# power.net
KiCad netlist of a schematic drawn in Altium Designer
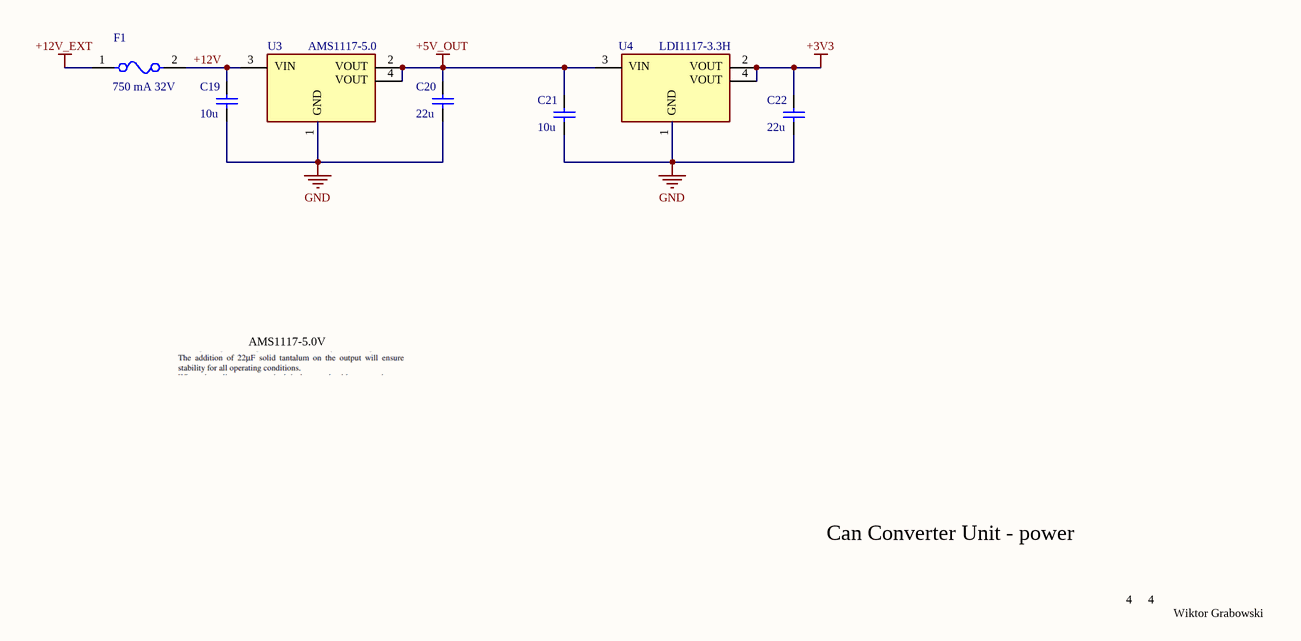
[diagram p0: power.SchDoc]

(export (version "E")
  (design (tool "Eeschema 10.0.6"))
  (components
    (comp (ref "C19")
      (value "10u")
      (footprint "CAPC1206(3216)170_M")
      (description "CAP 47nF 200V ±10% 1206 (3216 Metric) Thickness 1.7mm SMD")
      (fields (field (name "TOLERANCE") "Â±10%"))
      (libsource (lib "Altium Content Vault") (part "CAP"))
    )
    (comp (ref "C20")
      (value "22u")
      (footprint "CAPC1206(3216)170_M")
      (description "CAP 47nF 200V ±10% 1206 (3216 Metric) Thickness 1.7mm SMD")
      (fields (field (name "TOLERANCE") "Â±10%"))
      (libsource (lib "Altium Content Vault") (part "CAP"))
    )
    (comp (ref "C21")
      (value "10u")
      (footprint "CAPC1206(3216)170_M")
      (description "CAP 47nF 200V ±10% 1206 (3216 Metric) Thickness 1.7mm SMD")
      (fields (field (name "TOLERANCE") "Â±10%"))
      (libsource (lib "Altium Content Vault") (part "CAP"))
    )
    (comp (ref "C22")
      (value "22u")
      (footprint "CAPC1206(3216)170_M")
      (description "CAP 47nF 200V ±10% 1206 (3216 Metric) Thickness 1.7mm SMD")
      (fields (field (name "TOLERANCE") "Â±10%"))
      (libsource (lib "Altium Content Vault") (part "CAP"))
    )
    (comp (ref "F1")
      (value "750 mA 32V")
      (footprint "FP-0466-MFG")
      (description "FUSE BOARD MOUNT 750MA 63VAC/VDC")
      (libsource (lib "Altium Content Vault") (part "5bcf9b9f640e542cf0359d10258e979"))
    )
    (comp (ref "U3")
      (value "AMS1117-5.0")
      (footprint "AMS1117-5.0")
      (description "1A LOW DROPOUT VOLTAGE REGULATOR")
      (libsource (lib "HydrogreenLibrary") (part "AMS1117-5.0"))
    )
    (comp (ref "U4")
      (value "LDI1117-3.3H")
      (footprint "LDI1117-3.3H")
      (description "Fixed Positive LDO Regulator")
      (fields (field (name "MANUFACTURER") "Diotec"))
      (libsource (lib "HydrogreenLibrary") (part "LDI1117-3.3H"))
    )
  )
  (nets
    (net (code "1") (name "+3V3") (class "Default")
      (node (ref "C22") (pin "2") (pinfunction "2_2") (pintype "passive"))
      (node (ref "U4") (pin "2") (pintype "power_in"))
      (node (ref "U4") (pin "4") (pintype "power_in"))
    )
    (net (code "2") (name "+5V_OUT") (class "Default")
      (node (ref "C20") (pin "2") (pinfunction "2_2") (pintype "passive"))
      (node (ref "C21") (pin "2") (pinfunction "2_2") (pintype "passive"))
      (node (ref "U3") (pin "2") (pintype "power_in"))
      (node (ref "U3") (pin "4") (pintype "power_in"))
      (node (ref "U4") (pin "3") (pintype "power_in"))
    )
    (net (code "3") (name "+12V_EXT") (class "Default")
      (node (ref "F1") (pin "1") (pinfunction "1_1") (pintype "passive"))
    )
    (net (code "4") (name "/+12V") (class "Default")
      (node (ref "C19") (pin "2") (pinfunction "2_2") (pintype "passive"))
      (node (ref "F1") (pin "2") (pinfunction "2_2") (pintype "passive"))
      (node (ref "U3") (pin "3") (pintype "power_in"))
    )
    (net (code "5") (name "GND") (class "Default")
      (node (ref "C19") (pin "1") (pinfunction "1_1") (pintype "passive"))
      (node (ref "C20") (pin "1") (pinfunction "1_1") (pintype "passive"))
      (node (ref "C21") (pin "1") (pinfunction "1_1") (pintype "passive"))
      (node (ref "C22") (pin "1") (pinfunction "1_1") (pintype "passive"))
      (node (ref "U3") (pin "1") (pintype "passive"))
      (node (ref "U4") (pin "1") (pintype "passive"))
    )
  )
)
